# ATmega328p-DHT11-DS1307-LCD-StripBd.net
KiCad netlist of a schematic drawn in EAGLE
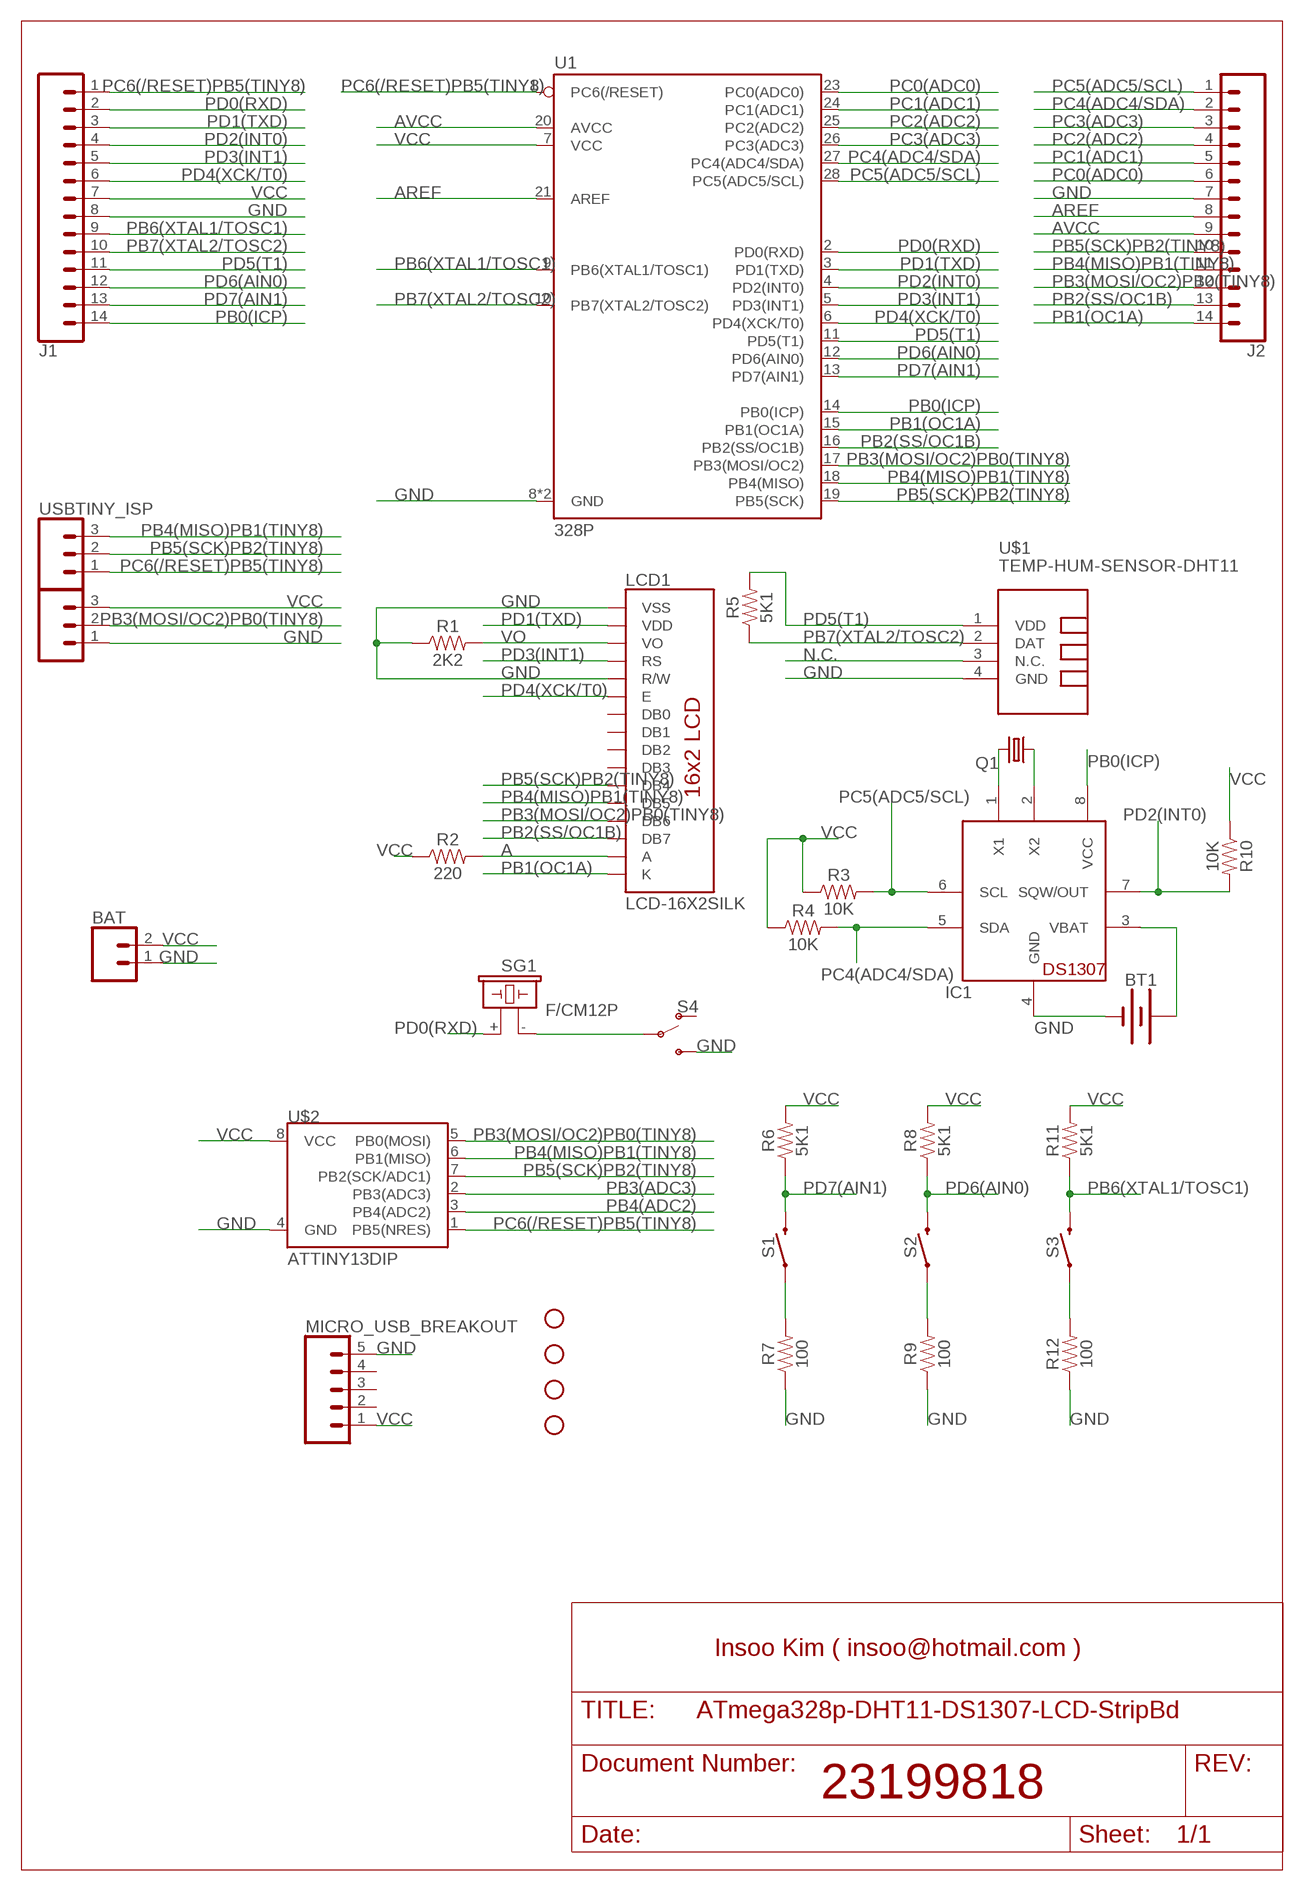
[diagram p0: schematic, sheet 1]

(export (version "E")
  (design (tool "Eeschema 10.0.6"))
  (components
    (comp (ref "BAT")
      (value "CONN_02")
      (footprint "eagle-import:1X02")
      (libsource (lib "eagle-import") (part "CONN_02"))
    )
    (comp (ref "BT1")
      (value "BATTERY-20MM_PTH")
      (footprint "eagle-import:BATTCOM_20MM_PTH")
      (libsource (lib "eagle-import") (part "BATTERY-20MM_PTH"))
    )
    (comp (ref "H1")
      (value "STAND-OFF")
      (footprint "eagle-import:STAND-OFF")
      (libsource (lib "eagle-import") (part "STAND-OFF"))
    )
    (comp (ref "H2")
      (value "STAND-OFF")
      (footprint "eagle-import:STAND-OFF")
      (libsource (lib "eagle-import") (part "STAND-OFF"))
    )
    (comp (ref "H3")
      (value "STAND-OFF")
      (footprint "eagle-import:STAND-OFF")
      (libsource (lib "eagle-import") (part "STAND-OFF"))
    )
    (comp (ref "H4")
      (value "STAND-OFF")
      (footprint "eagle-import:STAND-OFF")
      (libsource (lib "eagle-import") (part "STAND-OFF"))
    )
    (comp (ref "IC1")
      (value "DS1307")
      (footprint "eagle-import:DIL08")
      (libsource (lib "eagle-import") (part "DS1307"))
    )
    (comp (ref "J1")
      (value "CONN_14")
      (footprint "eagle-import:1X14")
      (libsource (lib "eagle-import") (part "CONN_14"))
    )
    (comp (ref "J2")
      (value "CONN_14")
      (footprint "eagle-import:1X14")
      (libsource (lib "eagle-import") (part "CONN_14"))
    )
    (comp (ref "J3")
      (value "455-1750-1-ND")
      (footprint "eagle-import:1X03")
      (libsource (lib "eagle-import") (part "CONN_03"))
    )
    (comp (ref "LCD1")
      (value "LCD-16X2SILK")
      (footprint "eagle-import:LCD-16X2")
      (libsource (lib "eagle-import") (part "LCD-16X2SILK"))
    )
    (comp (ref "MICRO_USB_BREAKOUT")
      (value "CONN_05")
      (footprint "eagle-import:1X05")
      (libsource (lib "eagle-import") (part "CONN_05"))
    )
    (comp (ref "Q1")
      (value "CRYSTALTC26H")
      (footprint "eagle-import:TC26H")
      (libsource (lib "eagle-import") (part "CRYSTALTC26H"))
    )
    (comp (ref "R1")
      (value "2K2")
      (footprint "eagle-import:AXIAL-0.3")
      (libsource (lib "eagle-import") (part "1KOHM-HORIZ-1/4W-5%"))
    )
    (comp (ref "R2")
      (value "220")
      (footprint "eagle-import:AXIAL-0.3")
      (libsource (lib "eagle-import") (part "1KOHM-HORIZ-1/4W-5%"))
    )
    (comp (ref "R3")
      (value "10K")
      (footprint "eagle-import:AXIAL-0.3")
      (libsource (lib "eagle-import") (part "1KOHM-HORIZ-1/4W-5%"))
    )
    (comp (ref "R4")
      (value "10K")
      (footprint "eagle-import:AXIAL-0.3")
      (libsource (lib "eagle-import") (part "1KOHM-HORIZ-1/4W-5%"))
    )
    (comp (ref "R5")
      (value "5K1")
      (footprint "eagle-import:AXIAL-0.3")
      (libsource (lib "eagle-import") (part "1KOHM-HORIZ-1/4W-5%"))
    )
    (comp (ref "R6")
      (value "5K1")
      (footprint "eagle-import:AXIAL-0.3")
      (libsource (lib "eagle-import") (part "1KOHM-HORIZ-1/4W-5%"))
    )
    (comp (ref "R7")
      (value "100")
      (footprint "eagle-import:AXIAL-0.3")
      (libsource (lib "eagle-import") (part "1KOHM-HORIZ-1/4W-5%"))
    )
    (comp (ref "R8")
      (value "5K1")
      (footprint "eagle-import:AXIAL-0.3")
      (libsource (lib "eagle-import") (part "1KOHM-HORIZ-1/4W-5%"))
    )
    (comp (ref "R9")
      (value "100")
      (footprint "eagle-import:AXIAL-0.3")
      (libsource (lib "eagle-import") (part "1KOHM-HORIZ-1/4W-5%"))
    )
    (comp (ref "R10")
      (value "10K")
      (footprint "eagle-import:AXIAL-0.3")
      (libsource (lib "eagle-import") (part "1KOHM-HORIZ-1/4W-5%"))
    )
    (comp (ref "R11")
      (value "5K1")
      (footprint "eagle-import:AXIAL-0.3")
      (libsource (lib "eagle-import") (part "1KOHM-HORIZ-1/4W-5%"))
    )
    (comp (ref "R12")
      (value "100")
      (footprint "eagle-import:AXIAL-0.3")
      (libsource (lib "eagle-import") (part "1KOHM-HORIZ-1/4W-5%"))
    )
    (comp (ref "S1")
      (value "MOMENTARY-SWITCH-SPST-PTH-12MM")
      (footprint "eagle-import:TACTILE_SWITCH_PTH_12MM")
      (libsource (lib "eagle-import") (part "MOMENTARY-SWITCH-SPST-PTH-12MM"))
    )
    (comp (ref "S2")
      (value "MOMENTARY-SWITCH-SPST-PTH-12MM")
      (footprint "eagle-import:TACTILE_SWITCH_PTH_12MM")
      (libsource (lib "eagle-import") (part "MOMENTARY-SWITCH-SPST-PTH-12MM"))
    )
    (comp (ref "S3")
      (value "MOMENTARY-SWITCH-SPST-PTH-12MM")
      (footprint "eagle-import:TACTILE_SWITCH_PTH_12MM")
      (libsource (lib "eagle-import") (part "MOMENTARY-SWITCH-SPST-PTH-12MM"))
    )
    (comp (ref "S4")
      (value "SWITCH-SPDT-PTH-11.6X4.0MM")
      (footprint "eagle-import:SWITCH_SPDT_PTH_11.6X4.0MM")
      (libsource (lib "eagle-import") (part "SWITCH-SPDT-PTH-11.6X4.0MM"))
    )
    (comp (ref "SG1")
      (value "F/CM12P")
      (footprint "eagle-import:F_CM12P")
      (libsource (lib "eagle-import") (part "F/CM12P"))
    )
    (comp (ref "U$1")
      (value "TEMP-HUM-SENSOR-DHT11")
      (footprint "eagle-import:TEMP-HUM-SENSOR-DHT11")
      (libsource (lib "eagle-import") (part "TEMP-HUM-SENSOR-DHT11"))
    )
    (comp (ref "U$2")
      (value "ATTINY13DIP")
      (footprint "eagle-import:DIP08_MCU")
      (libsource (lib "eagle-import") (part "ATTINY13DIP"))
    )
    (comp (ref "U1")
      (value "328P")
      (footprint "eagle-import:DIP28")
      (libsource (lib "eagle-import") (part "ATMEGA328P_PDIP"))
    )
    (comp (ref "USBTINY_ISP")
      (value "455-1750-1-ND")
      (footprint "eagle-import:1X03")
      (libsource (lib "eagle-import") (part "CONN_03"))
    )
  )
  (nets
    (net (code "1") (name "/A") (class "Default")
      (node (ref "LCD1") (pin "15") (pinfunction "A_15") (pintype "power_in"))
      (node (ref "R2") (pin "P$2") (pinfunction "2_P$2") (pintype "passive"))
    )
    (net (code "2") (name "/AREF") (class "Default")
      (node (ref "J2") (pin "8") (pinfunction "8_8") (pintype "passive"))
      (node (ref "U1") (pin "21") (pinfunction "AREF_21") (pintype "bidirectional"))
    )
    (net (code "3") (name "/AVCC") (class "Default")
      (node (ref "J2") (pin "9") (pinfunction "9_9") (pintype "passive"))
      (node (ref "U1") (pin "20") (pinfunction "AVCC_20") (pintype "bidirectional"))
    )
    (net (code "4") (name "/GND") (class "Default")
      (node (ref "BAT") (pin "1") (pinfunction "1_1") (pintype "passive"))
      (node (ref "BT1") (pin "2") (pinfunction "-_2") (pintype "power_in"))
      (node (ref "IC1") (pin "4") (pinfunction "GND_4") (pintype "power_in"))
      (node (ref "J1") (pin "8") (pinfunction "8_8") (pintype "passive"))
      (node (ref "J2") (pin "7") (pinfunction "7_7") (pintype "passive"))
      (node (ref "J3") (pin "1") (pinfunction "1_1") (pintype "passive"))
      (node (ref "LCD1") (pin "1") (pinfunction "VSS_1") (pintype "power_in"))
      (node (ref "LCD1") (pin "5") (pinfunction "R/W_5") (pintype "input"))
      (node (ref "MICRO_USB_BREAKOUT") (pin "5") (pinfunction "5_5") (pintype "passive"))
      (node (ref "R1") (pin "P$1") (pinfunction "1_P$1") (pintype "passive"))
      (node (ref "R12") (pin "P$1") (pinfunction "1_P$1") (pintype "passive"))
      (node (ref "R7") (pin "P$1") (pinfunction "1_P$1") (pintype "passive"))
      (node (ref "R9") (pin "P$1") (pinfunction "1_P$1") (pintype "passive"))
      (node (ref "S4") (pin "3") (pinfunction "S_3") (pintype "passive"))
      (node (ref "U$1") (pin "4") (pinfunction "GND_4") (pintype "power_in"))
      (node (ref "U$2") (pin "4") (pinfunction "GND_4") (pintype "bidirectional"))
      (node (ref "U1") (pin "22") (pinfunction "GND_22") (pintype "bidirectional"))
      (node (ref "U1") (pin "8") (pinfunction "GND_8") (pintype "bidirectional"))
    )
    (net (code "5") (name "/N.C.") (class "Default")
      (node (ref "U$1") (pin "3") (pinfunction "N.C._3") (pintype "passive"))
    )
    (net (code "6") (name "/PB0(ICP)") (class "Default")
      (node (ref "IC1") (pin "8") (pinfunction "VCC_8") (pintype "power_in"))
      (node (ref "J1") (pin "14") (pinfunction "14_14") (pintype "passive"))
      (node (ref "U1") (pin "14") (pinfunction "PB0(ICP)_14") (pintype "bidirectional"))
    )
    (net (code "7") (name "/PB1(OC1A)") (class "Default")
      (node (ref "J2") (pin "14") (pinfunction "14_14") (pintype "passive"))
      (node (ref "LCD1") (pin "16") (pinfunction "K_16") (pintype "power_in"))
      (node (ref "U1") (pin "15") (pinfunction "PB1(OC1A)_15") (pintype "bidirectional"))
    )
    (net (code "8") (name "/PB2(SS{slash}OC1B)") (class "Default")
      (node (ref "J2") (pin "13") (pinfunction "13_13") (pintype "passive"))
      (node (ref "LCD1") (pin "14") (pinfunction "DB7_14") (pintype "bidirectional"))
      (node (ref "U1") (pin "16") (pinfunction "PB2(SS/OC1B)_16") (pintype "bidirectional"))
    )
    (net (code "9") (name "/PB3(ADC3)") (class "Default")
      (node (ref "U$2") (pin "2") (pinfunction "PB3(ADC3)_2") (pintype "bidirectional"))
    )
    (net (code "10") (name "/PB3(MOSI{slash}OC2)PB0(TINY8)") (class "Default")
      (node (ref "J2") (pin "12") (pinfunction "12_12") (pintype "passive"))
      (node (ref "J3") (pin "2") (pinfunction "2_2") (pintype "passive"))
      (node (ref "LCD1") (pin "13") (pinfunction "DB6_13") (pintype "bidirectional"))
      (node (ref "U$2") (pin "5") (pinfunction "PB0(MOSI)_5") (pintype "bidirectional"))
      (node (ref "U1") (pin "17") (pinfunction "PB3(MOSI/OC2)_17") (pintype "bidirectional"))
    )
    (net (code "11") (name "/PB4(ADC2)") (class "Default")
      (node (ref "U$2") (pin "3") (pinfunction "PB4(ADC2)_3") (pintype "bidirectional"))
    )
    (net (code "12") (name "/PB4(MISO)PB1(TINY8)") (class "Default")
      (node (ref "J2") (pin "11") (pinfunction "11_11") (pintype "passive"))
      (node (ref "LCD1") (pin "12") (pinfunction "DB5_12") (pintype "bidirectional"))
      (node (ref "U$2") (pin "6") (pinfunction "PB1(MISO)_6") (pintype "bidirectional"))
      (node (ref "U1") (pin "18") (pinfunction "PB4(MISO)_18") (pintype "bidirectional"))
      (node (ref "USBTINY_ISP") (pin "3") (pinfunction "3_3") (pintype "passive"))
    )
    (net (code "13") (name "/PB5(SCK)PB2(TINY8)") (class "Default")
      (node (ref "J2") (pin "10") (pinfunction "10_10") (pintype "passive"))
      (node (ref "LCD1") (pin "11") (pinfunction "DB4_11") (pintype "bidirectional"))
      (node (ref "U$2") (pin "7") (pinfunction "PB2(SCK/ADC1)_7") (pintype "bidirectional"))
      (node (ref "U1") (pin "19") (pinfunction "PB5(SCK)_19") (pintype "bidirectional"))
      (node (ref "USBTINY_ISP") (pin "2") (pinfunction "2_2") (pintype "passive"))
    )
    (net (code "14") (name "/PB6(XTAL1{slash}TOSC1)") (class "Default")
      (node (ref "J1") (pin "9") (pinfunction "9_9") (pintype "passive"))
      (node (ref "R11") (pin "P$1") (pinfunction "1_P$1") (pintype "passive"))
      (node (ref "S3") (pin "3") (pinfunction "2_3") (pintype "passive"))
      (node (ref "U1") (pin "9") (pinfunction "PB6(XTAL1/TOSC1)_9") (pintype "bidirectional"))
    )
    (net (code "15") (name "/PB7(XTAL2{slash}TOSC2)") (class "Default")
      (node (ref "J1") (pin "10") (pinfunction "10_10") (pintype "passive"))
      (node (ref "R5") (pin "P$1") (pinfunction "1_P$1") (pintype "passive"))
      (node (ref "U$1") (pin "2") (pinfunction "DAT_2") (pintype "bidirectional"))
      (node (ref "U1") (pin "10") (pinfunction "PB7(XTAL2/TOSC2)_10") (pintype "bidirectional"))
    )
    (net (code "16") (name "/PC0(ADC0)") (class "Default")
      (node (ref "J2") (pin "6") (pinfunction "6_6") (pintype "passive"))
      (node (ref "U1") (pin "23") (pinfunction "PC0(ADC0)_23") (pintype "bidirectional"))
    )
    (net (code "17") (name "/PC1(ADC1)") (class "Default")
      (node (ref "J2") (pin "5") (pinfunction "5_5") (pintype "passive"))
      (node (ref "U1") (pin "24") (pinfunction "PC1(ADC1)_24") (pintype "bidirectional"))
    )
    (net (code "18") (name "/PC2(ADC2)") (class "Default")
      (node (ref "J2") (pin "4") (pinfunction "4_4") (pintype "passive"))
      (node (ref "U1") (pin "25") (pinfunction "PC2(ADC2)_25") (pintype "bidirectional"))
    )
    (net (code "19") (name "/PC3(ADC3)") (class "Default")
      (node (ref "J2") (pin "3") (pinfunction "3_3") (pintype "passive"))
      (node (ref "U1") (pin "26") (pinfunction "PC3(ADC3)_26") (pintype "bidirectional"))
    )
    (net (code "20") (name "/PC4(ADC4{slash}SDA)") (class "Default")
      (node (ref "IC1") (pin "5") (pinfunction "SDA_5") (pintype "bidirectional"))
      (node (ref "J2") (pin "2") (pinfunction "2_2") (pintype "passive"))
      (node (ref "R4") (pin "P$2") (pinfunction "2_P$2") (pintype "passive"))
      (node (ref "U1") (pin "27") (pinfunction "PC4(ADC4/SDA)_27") (pintype "bidirectional"))
    )
    (net (code "21") (name "/PC5(ADC5{slash}SCL)") (class "Default")
      (node (ref "IC1") (pin "6") (pinfunction "SCL_6") (pintype "bidirectional"))
      (node (ref "J2") (pin "1") (pinfunction "1_1") (pintype "passive"))
      (node (ref "R3") (pin "P$2") (pinfunction "2_P$2") (pintype "passive"))
      (node (ref "U1") (pin "28") (pinfunction "PC5(ADC5/SCL)_28") (pintype "bidirectional"))
    )
    (net (code "22") (name "/PC6({slash}RESET)PB5(TINY8)") (class "Default")
      (node (ref "J1") (pin "1") (pinfunction "1_1") (pintype "passive"))
      (node (ref "U$2") (pin "1") (pinfunction "PB5(NRES)_1") (pintype "bidirectional"))
      (node (ref "U1") (pin "1") (pinfunction "PC6(/RESET)_1") (pintype "bidirectional"))
      (node (ref "USBTINY_ISP") (pin "1") (pinfunction "1_1") (pintype "passive"))
    )
    (net (code "23") (name "/PD0(RXD)") (class "Default")
      (node (ref "J1") (pin "2") (pinfunction "2_2") (pintype "passive"))
      (node (ref "SG1") (pin "+") (pinfunction "1_+") (pintype "passive"))
      (node (ref "U1") (pin "2") (pinfunction "PD0(RXD)_2") (pintype "bidirectional"))
    )
    (net (code "24") (name "/PD1(TXD)") (class "Default")
      (node (ref "J1") (pin "3") (pinfunction "3_3") (pintype "passive"))
      (node (ref "LCD1") (pin "2") (pinfunction "VDD_2") (pintype "power_in"))
      (node (ref "U1") (pin "3") (pinfunction "PD1(TXD)_3") (pintype "bidirectional"))
    )
    (net (code "25") (name "/PD2(INT0)") (class "Default")
      (node (ref "IC1") (pin "7") (pinfunction "SQW/OUT_7") (pintype "bidirectional"))
      (node (ref "J1") (pin "4") (pinfunction "4_4") (pintype "passive"))
      (node (ref "R10") (pin "P$2") (pinfunction "2_P$2") (pintype "passive"))
      (node (ref "U1") (pin "4") (pinfunction "PD2(INT0)_4") (pintype "bidirectional"))
    )
    (net (code "26") (name "/PD3(INT1)") (class "Default")
      (node (ref "J1") (pin "5") (pinfunction "5_5") (pintype "passive"))
      (node (ref "LCD1") (pin "4") (pinfunction "RS_4") (pintype "input"))
      (node (ref "U1") (pin "5") (pinfunction "PD3(INT1)_5") (pintype "bidirectional"))
    )
    (net (code "27") (name "/PD4(XCK{slash}T0)") (class "Default")
      (node (ref "J1") (pin "6") (pinfunction "6_6") (pintype "passive"))
      (node (ref "LCD1") (pin "6") (pinfunction "E_6") (pintype "input"))
      (node (ref "U1") (pin "6") (pinfunction "PD4(XCK/T0)_6") (pintype "bidirectional"))
    )
    (net (code "28") (name "/PD5(T1)") (class "Default")
      (node (ref "J1") (pin "11") (pinfunction "11_11") (pintype "passive"))
      (node (ref "R5") (pin "P$2") (pinfunction "2_P$2") (pintype "passive"))
      (node (ref "U$1") (pin "1") (pinfunction "VDD_1") (pintype "power_in"))
      (node (ref "U1") (pin "11") (pinfunction "PD5(T1)_11") (pintype "bidirectional"))
    )
    (net (code "29") (name "/PD6(AIN0)") (class "Default")
      (node (ref "J1") (pin "12") (pinfunction "12_12") (pintype "passive"))
      (node (ref "R8") (pin "P$1") (pinfunction "1_P$1") (pintype "passive"))
      (node (ref "S2") (pin "3") (pinfunction "2_3") (pintype "passive"))
      (node (ref "U1") (pin "12") (pinfunction "PD6(AIN0)_12") (pintype "bidirectional"))
    )
    (net (code "30") (name "/PD7(AIN1)") (class "Default")
      (node (ref "J1") (pin "13") (pinfunction "13_13") (pintype "passive"))
      (node (ref "R6") (pin "P$1") (pinfunction "1_P$1") (pintype "passive"))
      (node (ref "S1") (pin "3") (pinfunction "2_3") (pintype "passive"))
      (node (ref "U1") (pin "13") (pinfunction "PD7(AIN1)_13") (pintype "bidirectional"))
    )
    (net (code "31") (name "/VCC") (class "Default")
      (node (ref "BAT") (pin "2") (pinfunction "2_2") (pintype "passive"))
      (node (ref "J1") (pin "7") (pinfunction "7_7") (pintype "passive"))
      (node (ref "J3") (pin "3") (pinfunction "3_3") (pintype "passive"))
      (node (ref "MICRO_USB_BREAKOUT") (pin "1") (pinfunction "1_1") (pintype "passive"))
      (node (ref "R10") (pin "P$1") (pinfunction "1_P$1") (pintype "passive"))
      (node (ref "R11") (pin "P$2") (pinfunction "2_P$2") (pintype "passive"))
      (node (ref "R2") (pin "P$1") (pinfunction "1_P$1") (pintype "passive"))
      (node (ref "R3") (pin "P$1") (pinfunction "1_P$1") (pintype "passive"))
      (node (ref "R4") (pin "P$1") (pinfunction "1_P$1") (pintype "passive"))
      (node (ref "R6") (pin "P$2") (pinfunction "2_P$2") (pintype "passive"))
      (node (ref "R8") (pin "P$2") (pinfunction "2_P$2") (pintype "passive"))
      (node (ref "U$2") (pin "8") (pinfunction "VCC_8") (pintype "bidirectional"))
      (node (ref "U1") (pin "7") (pinfunction "VCC_7") (pintype "bidirectional"))
    )
    (net (code "32") (name "/VO") (class "Default")
      (node (ref "LCD1") (pin "3") (pinfunction "VO_3") (pintype "bidirectional"))
      (node (ref "R1") (pin "P$2") (pinfunction "2_P$2") (pintype "passive"))
    )
    (net (code "33") (name "Net-(BT1-+)") (class "Default")
      (node (ref "BT1") (pin "1") (pinfunction "+_1") (pintype "power_in"))
      (node (ref "IC1") (pin "3") (pinfunction "VBAT_3") (pintype "power_in"))
    )
    (net (code "34") (name "Net-(IC1-X1)") (class "Default")
      (node (ref "IC1") (pin "1") (pinfunction "X1_1") (pintype "passive"))
      (node (ref "Q1") (pin "2") (pinfunction "2_2") (pintype "passive"))
    )
    (net (code "35") (name "Net-(IC1-X2)") (class "Default")
      (node (ref "IC1") (pin "2") (pinfunction "X2_2") (pintype "passive"))
      (node (ref "Q1") (pin "1") (pinfunction "1_1") (pintype "passive"))
    )
    (net (code "36") (name "Net-(R7-2)") (class "Default")
      (node (ref "R7") (pin "P$2") (pinfunction "2_P$2") (pintype "passive"))
      (node (ref "S1") (pin "1") (pinfunction "1_1") (pintype "passive"))
    )
    (net (code "37") (name "Net-(R9-2)") (class "Default")
      (node (ref "R9") (pin "P$2") (pinfunction "2_P$2") (pintype "passive"))
      (node (ref "S2") (pin "1") (pinfunction "1_1") (pintype "passive"))
    )
    (net (code "38") (name "Net-(R12-2)") (class "Default")
      (node (ref "R12") (pin "P$2") (pinfunction "2_P$2") (pintype "passive"))
      (node (ref "S3") (pin "1") (pinfunction "1_1") (pintype "passive"))
    )
    (net (code "39") (name "Net-(S4-P)") (class "Default")
      (node (ref "S4") (pin "2") (pinfunction "P_2") (pintype "passive"))
      (node (ref "SG1") (pin "-") (pinfunction "2_-") (pintype "passive"))
    )
    (net (code "40") (name "unconnected-(LCD1-DB0-Pad7)") (class "Default")
      (node (ref "LCD1") (pin "7") (pinfunction "DB0_7") (pintype "bidirectional"))
    )
    (net (code "41") (name "unconnected-(LCD1-DB1-Pad8)") (class "Default")
      (node (ref "LCD1") (pin "8") (pinfunction "DB1_8") (pintype "bidirectional"))
    )
    (net (code "42") (name "unconnected-(LCD1-DB2-Pad9)") (class "Default")
      (node (ref "LCD1") (pin "9") (pinfunction "DB2_9") (pintype "bidirectional"))
    )
    (net (code "43") (name "unconnected-(LCD1-DB3-Pad10)") (class "Default")
      (node (ref "LCD1") (pin "10") (pinfunction "DB3_10") (pintype "bidirectional"))
    )
    (net (code "44") (name "unconnected-(MICRO_USB_BREAKOUT-Pad2)") (class "Default")
      (node (ref "MICRO_USB_BREAKOUT") (pin "2") (pinfunction "2_2") (pintype "passive"))
    )
    (net (code "45") (name "unconnected-(MICRO_USB_BREAKOUT-Pad3)") (class "Default")
      (node (ref "MICRO_USB_BREAKOUT") (pin "3") (pinfunction "3_3") (pintype "passive"))
    )
    (net (code "46") (name "unconnected-(MICRO_USB_BREAKOUT-Pad4)") (class "Default")
      (node (ref "MICRO_USB_BREAKOUT") (pin "4") (pinfunction "4_4") (pintype "passive"))
    )
    (net (code "47") (name "unconnected-(S4-O-Pad1)") (class "Default")
      (node (ref "S4") (pin "1") (pinfunction "O_1") (pintype "passive"))
    )
  )
)
